# led_driver.net
KiCad netlist of a schematic drawn in Altium Designer
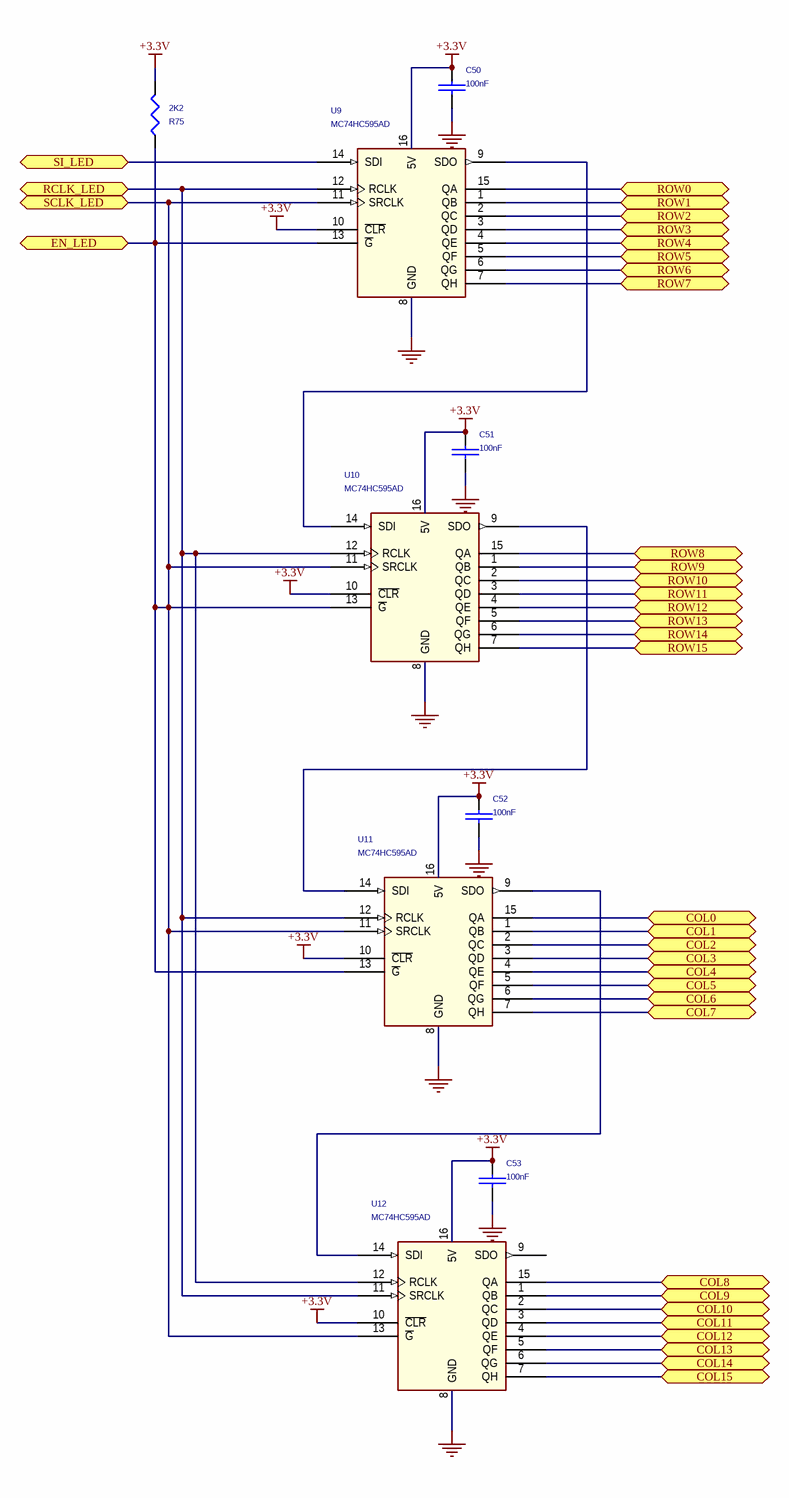
[diagram p0: led_driver.SchDoc]

(export (version "E")
  (design (tool "Eeschema 10.0.6"))
  (components
    (comp (ref "C50")
      (value "100nF")
      (footprint "0603_[1608]")
      (description "CER 50V X7R")
      (libsource (lib "*") (part "C"))
    )
    (comp (ref "C51")
      (value "100nF")
      (footprint "0603_[1608]")
      (description "CER 50V X7R")
      (libsource (lib "*") (part "C"))
    )
    (comp (ref "C52")
      (value "100nF")
      (footprint "0603_[1608]")
      (description "CER 50V X7R")
      (libsource (lib "*") (part "C"))
    )
    (comp (ref "C53")
      (value "100nF")
      (footprint "0603_[1608]")
      (description "CER 50V X7R")
      (libsource (lib "*") (part "C"))
    )
    (comp (ref "R75")
      (value "2K2")
      (footprint "0603_[1608]")
      (description "Resistor")
      (libsource (lib "*") (part "R_0"))
    )
    (comp (ref "U9")
      (value "MC74HC595AD")
      (footprint "SOIC16")
      (description "8-Bit Serial-Input/Serial or Prallel-Output Shift Register with Latched 3-State Outputs")
      (libsource (lib "*") (part "74HC595_27"))
    )
    (comp (ref "U10")
      (value "MC74HC595AD")
      (footprint "SOIC16")
      (description "8-Bit Serial-Input/Serial or Prallel-Output Shift Register with Latched 3-State Outputs")
      (libsource (lib "*") (part "74HC595_27"))
    )
    (comp (ref "U11")
      (value "MC74HC595AD")
      (footprint "SOIC16")
      (description "8-Bit Serial-Input/Serial or Prallel-Output Shift Register with Latched 3-State Outputs")
      (libsource (lib "*") (part "74HC595_27"))
    )
    (comp (ref "U12")
      (value "MC74HC595AD")
      (footprint "SOIC16")
      (description "8-Bit Serial-Input/Serial or Prallel-Output Shift Register with Latched 3-State Outputs")
      (libsource (lib "*") (part "74HC595_27"))
    )
  )
  (nets
    (net (code "1") (name "+3.3V") (class "Default")
      (node (ref "C50") (pin "1") (pinfunction "1_1") (pintype "passive"))
      (node (ref "C51") (pin "1") (pinfunction "1_1") (pintype "passive"))
      (node (ref "C52") (pin "1") (pinfunction "1_1") (pintype "passive"))
      (node (ref "C53") (pin "1") (pinfunction "1_1") (pintype "passive"))
      (node (ref "R75") (pin "1") (pinfunction "1_1") (pintype "passive"))
      (node (ref "U10") (pin "10") (pinfunction "~{CLR}_10") (pintype "passive"))
      (node (ref "U10") (pin "16") (pinfunction "5V_16") (pintype "power_in"))
      (node (ref "U11") (pin "10") (pinfunction "~{CLR}_10") (pintype "passive"))
      (node (ref "U11") (pin "16") (pinfunction "5V_16") (pintype "power_in"))
      (node (ref "U12") (pin "10") (pinfunction "~{CLR}_10") (pintype "passive"))
      (node (ref "U12") (pin "16") (pinfunction "5V_16") (pintype "power_in"))
      (node (ref "U9") (pin "10") (pinfunction "~{CLR}_10") (pintype "passive"))
      (node (ref "U9") (pin "16") (pinfunction "5V_16") (pintype "power_in"))
    )
    (net (code "2") (name "/COL0") (class "Default")
      (node (ref "U11") (pin "15") (pinfunction "QA_15") (pintype "tri_state"))
    )
    (net (code "3") (name "/COL1") (class "Default")
      (node (ref "U11") (pin "1") (pinfunction "QB_1") (pintype "tri_state"))
    )
    (net (code "4") (name "/COL2") (class "Default")
      (node (ref "U11") (pin "2") (pinfunction "QC_2") (pintype "tri_state"))
    )
    (net (code "5") (name "/COL3") (class "Default")
      (node (ref "U11") (pin "3") (pinfunction "QD_3") (pintype "tri_state"))
    )
    (net (code "6") (name "/COL4") (class "Default")
      (node (ref "U11") (pin "4") (pinfunction "QE_4") (pintype "tri_state"))
    )
    (net (code "7") (name "/COL5") (class "Default")
      (node (ref "U11") (pin "5") (pinfunction "QF_5") (pintype "tri_state"))
    )
    (net (code "8") (name "/COL6") (class "Default")
      (node (ref "U11") (pin "6") (pinfunction "QG_6") (pintype "tri_state"))
    )
    (net (code "9") (name "/COL7") (class "Default")
      (node (ref "U11") (pin "7") (pinfunction "QH_7") (pintype "tri_state"))
    )
    (net (code "10") (name "/COL8") (class "Default")
      (node (ref "U12") (pin "15") (pinfunction "QA_15") (pintype "tri_state"))
    )
    (net (code "11") (name "/COL9") (class "Default")
      (node (ref "U12") (pin "1") (pinfunction "QB_1") (pintype "tri_state"))
    )
    (net (code "12") (name "/COL10") (class "Default")
      (node (ref "U12") (pin "2") (pinfunction "QC_2") (pintype "tri_state"))
    )
    (net (code "13") (name "/COL11") (class "Default")
      (node (ref "U12") (pin "3") (pinfunction "QD_3") (pintype "tri_state"))
    )
    (net (code "14") (name "/COL12") (class "Default")
      (node (ref "U12") (pin "4") (pinfunction "QE_4") (pintype "tri_state"))
    )
    (net (code "15") (name "/COL13") (class "Default")
      (node (ref "U12") (pin "5") (pinfunction "QF_5") (pintype "tri_state"))
    )
    (net (code "16") (name "/COL14") (class "Default")
      (node (ref "U12") (pin "6") (pinfunction "QG_6") (pintype "tri_state"))
    )
    (net (code "17") (name "/COL15") (class "Default")
      (node (ref "U12") (pin "7") (pinfunction "QH_7") (pintype "tri_state"))
    )
    (net (code "18") (name "/EN_LED") (class "Default")
      (node (ref "R75") (pin "2") (pinfunction "2_2") (pintype "passive"))
      (node (ref "U10") (pin "11") (pinfunction "SRCLK_11") (pintype "input"))
      (node (ref "U10") (pin "13") (pinfunction "~{G}_13") (pintype "passive"))
      (node (ref "U11") (pin "11") (pinfunction "SRCLK_11") (pintype "input"))
      (node (ref "U11") (pin "13") (pinfunction "~{G}_13") (pintype "passive"))
      (node (ref "U12") (pin "13") (pinfunction "~{G}_13") (pintype "passive"))
      (node (ref "U9") (pin "11") (pinfunction "SRCLK_11") (pintype "input"))
      (node (ref "U9") (pin "13") (pinfunction "~{G}_13") (pintype "passive"))
    )
    (net (code "19") (name "/RCLK_LED") (class "Default")
      (node (ref "U10") (pin "12") (pinfunction "RCLK_12") (pintype "input"))
      (node (ref "U11") (pin "12") (pinfunction "RCLK_12") (pintype "input"))
      (node (ref "U12") (pin "11") (pinfunction "SRCLK_11") (pintype "input"))
      (node (ref "U12") (pin "12") (pinfunction "RCLK_12") (pintype "input"))
      (node (ref "U9") (pin "12") (pinfunction "RCLK_12") (pintype "input"))
    )
    (net (code "20") (name "/ROW0") (class "Default")
      (node (ref "U9") (pin "15") (pinfunction "QA_15") (pintype "tri_state"))
    )
    (net (code "21") (name "/ROW1") (class "Default")
      (node (ref "U9") (pin "1") (pinfunction "QB_1") (pintype "tri_state"))
    )
    (net (code "22") (name "/ROW2") (class "Default")
      (node (ref "U9") (pin "2") (pinfunction "QC_2") (pintype "tri_state"))
    )
    (net (code "23") (name "/ROW3") (class "Default")
      (node (ref "U9") (pin "3") (pinfunction "QD_3") (pintype "tri_state"))
    )
    (net (code "24") (name "/ROW4") (class "Default")
      (node (ref "U9") (pin "4") (pinfunction "QE_4") (pintype "tri_state"))
    )
    (net (code "25") (name "/ROW5") (class "Default")
      (node (ref "U9") (pin "5") (pinfunction "QF_5") (pintype "tri_state"))
    )
    (net (code "26") (name "/ROW6") (class "Default")
      (node (ref "U9") (pin "6") (pinfunction "QG_6") (pintype "tri_state"))
    )
    (net (code "27") (name "/ROW7") (class "Default")
      (node (ref "U9") (pin "7") (pinfunction "QH_7") (pintype "tri_state"))
    )
    (net (code "28") (name "/ROW8") (class "Default")
      (node (ref "U10") (pin "15") (pinfunction "QA_15") (pintype "tri_state"))
    )
    (net (code "29") (name "/ROW9") (class "Default")
      (node (ref "U10") (pin "1") (pinfunction "QB_1") (pintype "tri_state"))
    )
    (net (code "30") (name "/ROW10") (class "Default")
      (node (ref "U10") (pin "2") (pinfunction "QC_2") (pintype "tri_state"))
    )
    (net (code "31") (name "/ROW11") (class "Default")
      (node (ref "U10") (pin "3") (pinfunction "QD_3") (pintype "tri_state"))
    )
    (net (code "32") (name "/ROW12") (class "Default")
      (node (ref "U10") (pin "4") (pinfunction "QE_4") (pintype "tri_state"))
    )
    (net (code "33") (name "/ROW13") (class "Default")
      (node (ref "U10") (pin "5") (pinfunction "QF_5") (pintype "tri_state"))
    )
    (net (code "34") (name "/ROW14") (class "Default")
      (node (ref "U10") (pin "6") (pinfunction "QG_6") (pintype "tri_state"))
    )
    (net (code "35") (name "/ROW15") (class "Default")
      (node (ref "U10") (pin "7") (pinfunction "QH_7") (pintype "tri_state"))
    )
    (net (code "36") (name "/SI_LED") (class "Default")
      (node (ref "U9") (pin "14") (pinfunction "SDI_14") (pintype "input"))
    )
    (net (code "37") (name "GND") (class "Default")
      (node (ref "C50") (pin "2") (pinfunction "2_2") (pintype "passive"))
      (node (ref "C51") (pin "2") (pinfunction "2_2") (pintype "passive"))
      (node (ref "C52") (pin "2") (pinfunction "2_2") (pintype "passive"))
      (node (ref "C53") (pin "2") (pinfunction "2_2") (pintype "passive"))
      (node (ref "U10") (pin "8") (pinfunction "GND_8") (pintype "power_in"))
      (node (ref "U11") (pin "8") (pinfunction "GND_8") (pintype "power_in"))
      (node (ref "U12") (pin "8") (pinfunction "GND_8") (pintype "power_in"))
      (node (ref "U9") (pin "8") (pinfunction "GND_8") (pintype "power_in"))
    )
    (net (code "38") (name "Net-(U10-SDI)") (class "Default")
      (node (ref "U10") (pin "14") (pinfunction "SDI_14") (pintype "input"))
      (node (ref "U9") (pin "9") (pinfunction "SDO_9") (pintype "output"))
    )
    (net (code "39") (name "Net-(U10-SDO)") (class "Default")
      (node (ref "U10") (pin "9") (pinfunction "SDO_9") (pintype "output"))
      (node (ref "U11") (pin "14") (pinfunction "SDI_14") (pintype "input"))
    )
    (net (code "40") (name "Net-(U11-SDO)") (class "Default")
      (node (ref "U11") (pin "9") (pinfunction "SDO_9") (pintype "output"))
      (node (ref "U12") (pin "14") (pinfunction "SDI_14") (pintype "input"))
    )
    (net (code "41") (name "unconnected-(U12-SDO-Pad9)") (class "Default")
      (node (ref "U12") (pin "9") (pinfunction "SDO_9") (pintype "output"))
    )
  )
)
